# Server_USB.net
KiCad netlist of a schematic drawn in Altium Designer
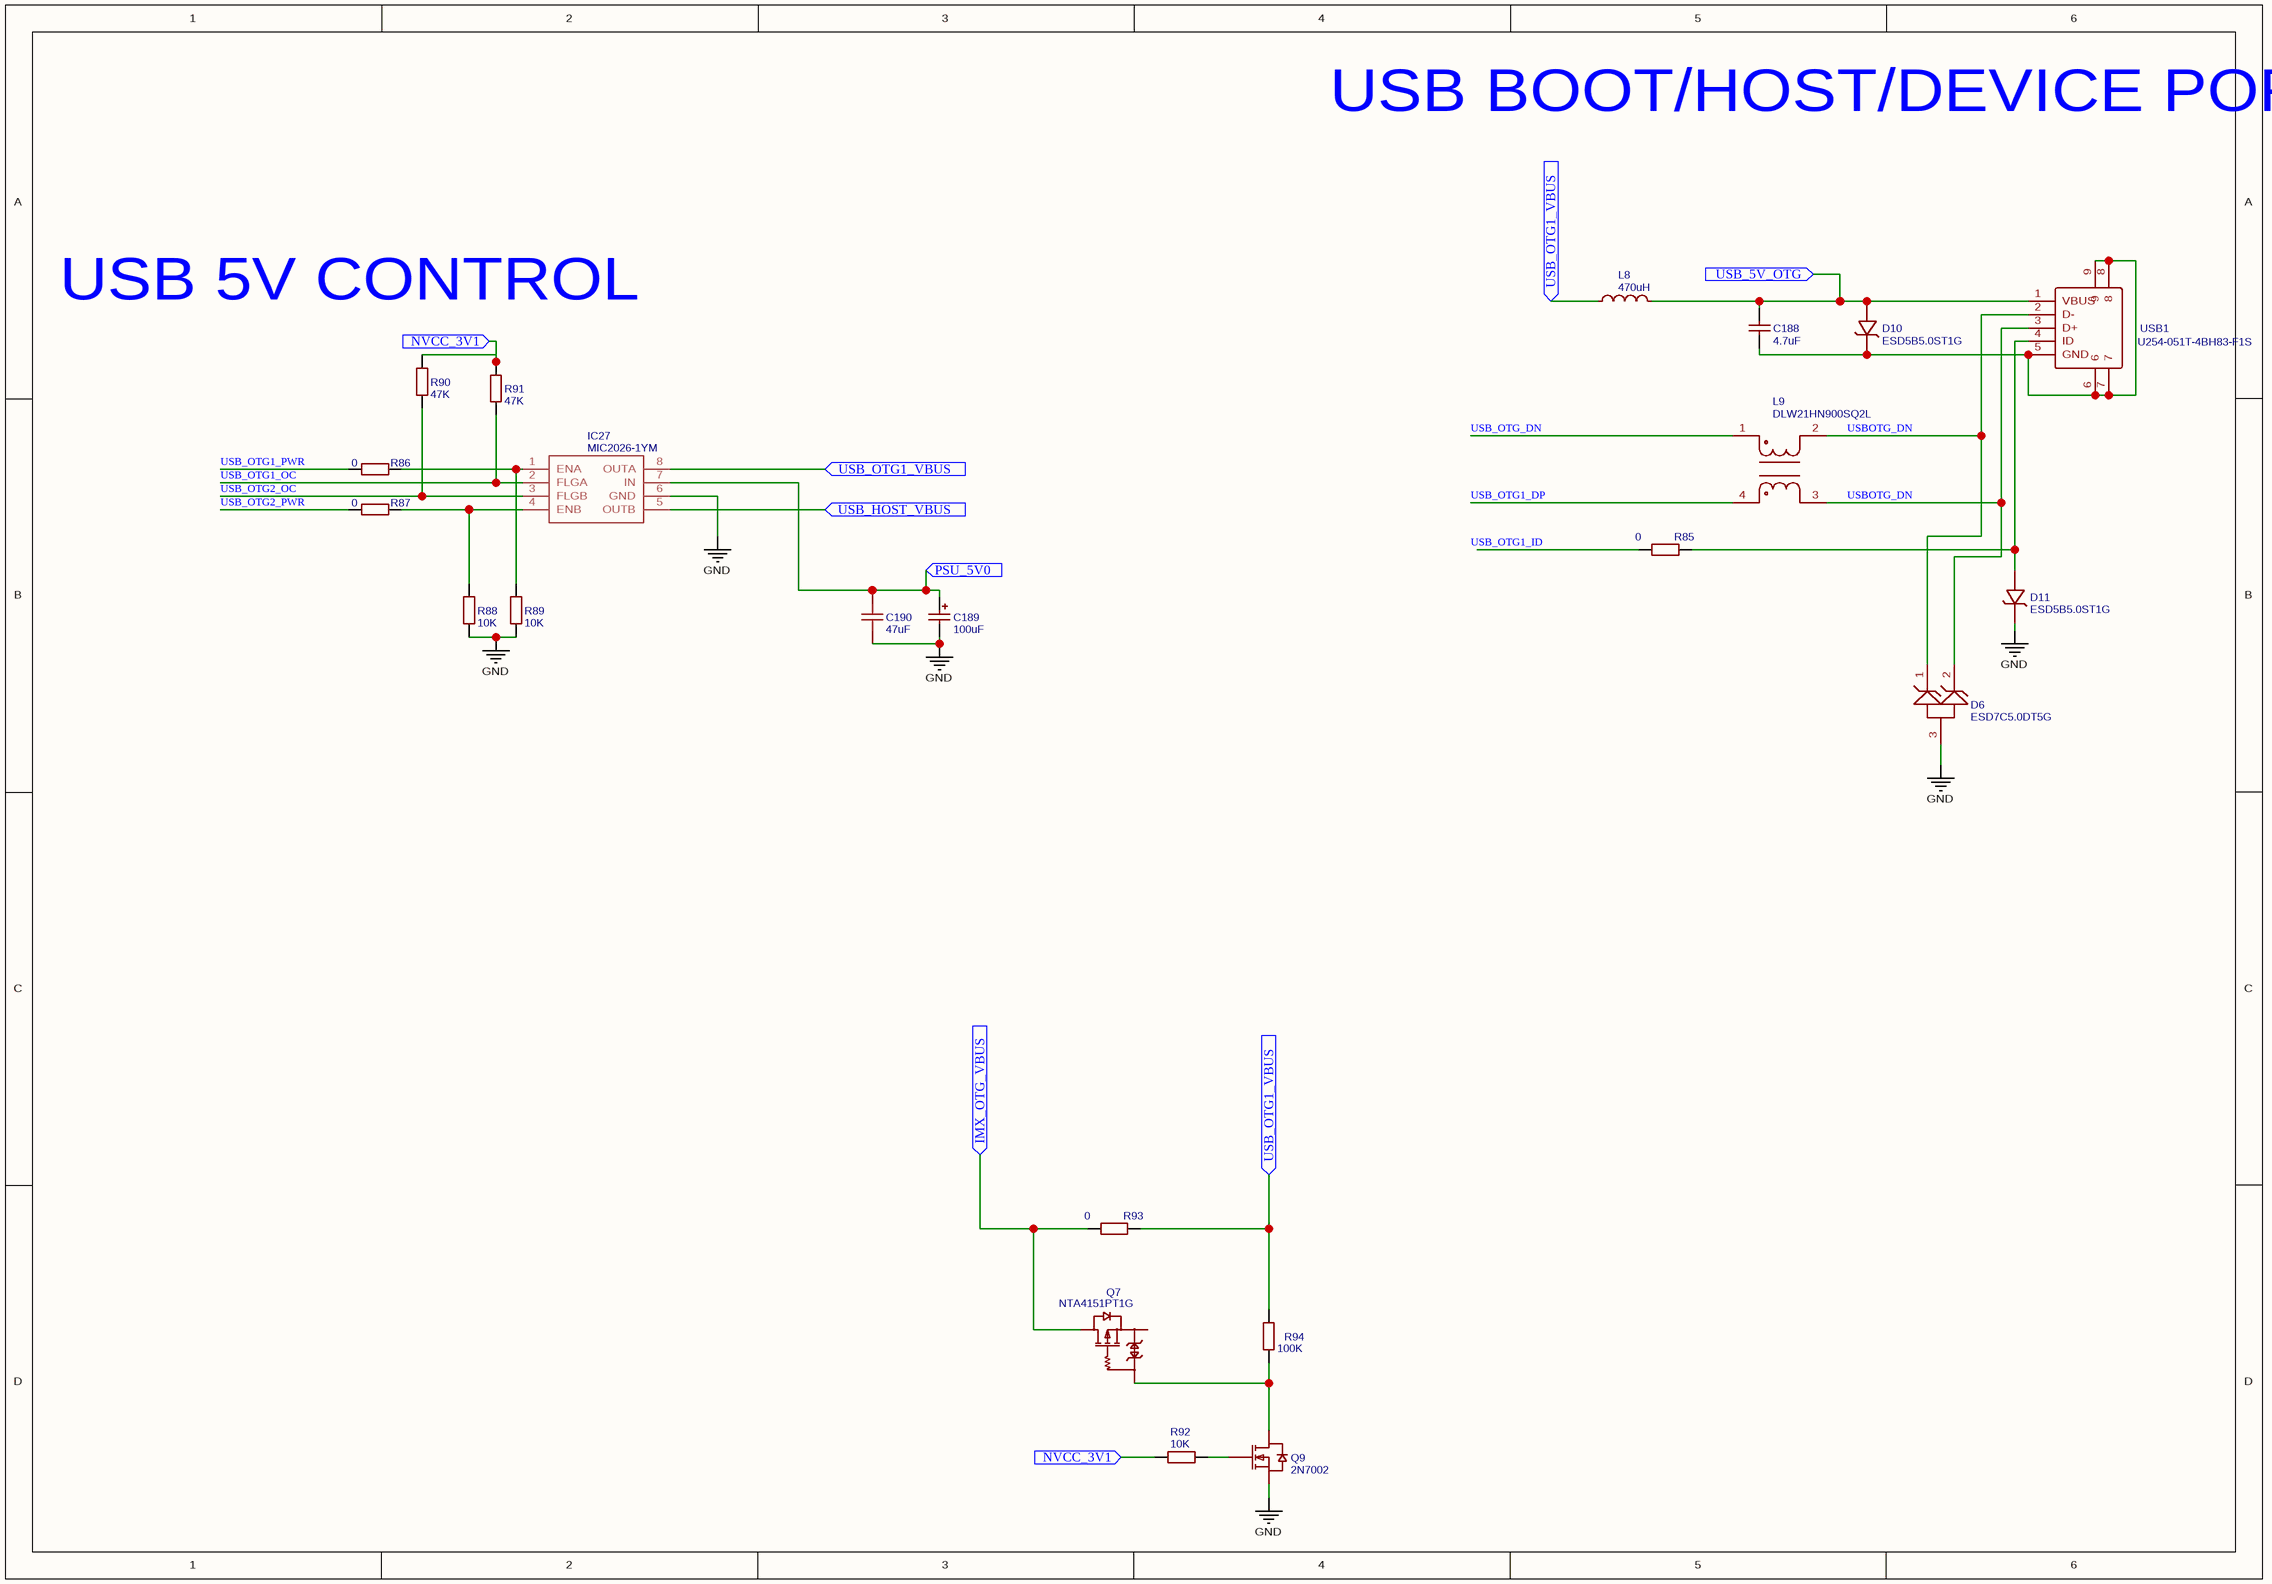
[diagram p0: Server USB.schdoc]

(export (version "E")
  (design (tool "Eeschema 10.0.6"))
  (components
    (comp (ref "C188")
      (value "4.7uF")
      (fields
        (field (name "BOM_MANUFACTURER PART") "CL05A475MP5NRNC")
        (field (name "BOM_SUPPLIER PART") "C23733")
      )
      (libsource (lib "altium-import") (part "root_1_4.7uF_"))
    )
    (comp (ref "C189")
      (value "100uF")
      (fields
        (field (name "BOM_MANUFACTURER PART") "TAJE107M025RNJ")
        (field (name "BOM_SUPPLIER PART") "C7230")
      )
      (libsource (lib "altium-import") (part "root_1_100uF_"))
    )
    (comp (ref "C190")
      (value "47uF")
      (fields
        (field (name "BOM_MANUFACTURER PART") "CL31A476MPHNNNE")
        (field (name "BOM_SUPPLIER PART") "C96123")
      )
      (libsource (lib "altium-import") (part "root_1_47uF_"))
    )
    (comp (ref "D6") (value "ESD7C5.0DT5G") (libsource (lib "altium-import") (part "root_1_ESD7C5.0DT5G_")))
    (comp (ref "D10")
      (value "ESD5B5.0ST1G")
      (fields (field (name "BOM_SUPPLIER PART") "C93623"))
      (libsource (lib "altium-import") (part "root_1_ESD5B5.0ST1G_"))
    )
    (comp (ref "D11")
      (value "ESD5B5.0ST1G")
      (fields (field (name "BOM_SUPPLIER PART") "C93623"))
      (libsource (lib "altium-import") (part "root_1_ESD5B5.0ST1G_"))
    )
    (comp (ref "IC27")
      (value "MIC2026-1YM")
      (fields (field (name "CONTRIBUTOR") "Ke'Ondrae_Mell"))
      (libsource (lib "altium-import") (part "root_0_MIC2026-1YM_"))
    )
    (comp (ref "L8")
      (value "470uH")
      (fields
        (field (name "BOM_SUPPLIER PART") "C169393")
        (field (name "BOM_MANUFACTURER PART") "SWRB1205S-471MT")
        (field (name "CONTRIBUTOR") "LCSC")
      )
      (libsource (lib "altium-import") (part "root_0_470uH_"))
    )
    (comp (ref "L9")
      (value "DLW21HN900SQ2L")
      (fields (field (name "BOM_SUPPLIER PART") "C97235"))
      (libsource (lib "altium-import") (part "root_0_DLW21HN900SQ2L_"))
    )
    (comp (ref "Q7")
      (value "NTA4151PT1G")
      (fields (field (name "BOM_SUPPLIER PART") "C54876"))
      (libsource (lib "altium-import") (part "root_1_NTA4151PT1G_"))
    )
    (comp (ref "Q9")
      (value "2N7002")
      (fields (field (name "BOM_SUPPLIER PART") "C8545"))
      (libsource (lib "altium-import") (part "root_0_2N7002_"))
    )
    (comp (ref "R85")
      (value "0")
      (fields
        (field (name "BOM_MANUFACTURER PART") "RK73Z1ETTP")
        (field (name "BOM_SUPPLIER PART") "C131359")
      )
      (libsource (lib "altium-import") (part "root_0_0_"))
    )
    (comp (ref "R86")
      (value "0")
      (fields
        (field (name "BOM_MANUFACTURER PART") "RK73Z1ETTP")
        (field (name "BOM_SUPPLIER PART") "C131359")
      )
      (libsource (lib "altium-import") (part "root_0_0_"))
    )
    (comp (ref "R87")
      (value "0")
      (fields
        (field (name "BOM_MANUFACTURER PART") "RK73Z1ETTP")
        (field (name "BOM_SUPPLIER PART") "C131359")
      )
      (libsource (lib "altium-import") (part "root_0_0_"))
    )
    (comp (ref "R88")
      (value "10K")
      (fields
        (field (name "BOM_MANUFACTURER PART") "0603WAF1002T5E")
        (field (name "BOM_SUPPLIER PART") "C25804")
      )
      (libsource (lib "altium-import") (part "root_1_10K_"))
    )
    (comp (ref "R89")
      (value "10K")
      (fields
        (field (name "BOM_MANUFACTURER PART") "0603WAF1002T5E")
        (field (name "BOM_SUPPLIER PART") "C25804")
      )
      (libsource (lib "altium-import") (part "root_1_10K_"))
    )
    (comp (ref "R90")
      (value "47K")
      (fields
        (field (name "BOM_MANUFACTURER PART") "0603WAF4702T5E")
        (field (name "BOM_SUPPLIER PART") "C25819")
      )
      (libsource (lib "altium-import") (part "root_1_47K_"))
    )
    (comp (ref "R91")
      (value "47K")
      (fields
        (field (name "BOM_MANUFACTURER PART") "0603WAF4702T5E")
        (field (name "BOM_SUPPLIER PART") "C25819")
      )
      (libsource (lib "altium-import") (part "root_1_47K_"))
    )
    (comp (ref "R92")
      (value "10K")
      (fields
        (field (name "BOM_MANUFACTURER PART") "0603WAF1002T5E")
        (field (name "BOM_SUPPLIER PART") "C25804")
      )
      (libsource (lib "altium-import") (part "root_2_10K_"))
    )
    (comp (ref "R93")
      (value "0")
      (fields
        (field (name "BOM_MANUFACTURER PART") "RK73Z1ETTP")
        (field (name "BOM_SUPPLIER PART") "C131359")
      )
      (libsource (lib "altium-import") (part "root_0_0_"))
    )
    (comp (ref "R94")
      (value "100K")
      (fields
        (field (name "BOM_MANUFACTURER PART") "0603WAF1003T5E")
        (field (name "BOM_SUPPLIER PART") "C25803")
      )
      (libsource (lib "altium-import") (part "root_1_100K_"))
    )
    (comp (ref "USB1")
      (value "U254-051T-4BH83-F1S")
      (fields (field (name "BOM_SUPPLIER PART") "C397452") (field (name "CONTRIBUTOR") "LCSC"))
      (libsource (lib "altium-import") (part "root_0_U254-051T-4BH83-F1S_"))
    )
  )
  (nets
    (net (code "1") (name "/IMX_OTG_VBUS") (class "Default")
      (node (ref "Q7") (pin "3") (pinfunction "D_3") (pintype "passive"))
      (node (ref "R93") (pin "1") (pinfunction "1_1") (pintype "passive"))
    )
    (net (code "2") (name "/NVCC_3V1") (class "Default")
      (node (ref "R90") (pin "2") (pinfunction "2_2") (pintype "passive"))
      (node (ref "R91") (pin "2") (pinfunction "2_2") (pintype "passive"))
      (node (ref "R92") (pin "2") (pinfunction "2_2") (pintype "passive"))
    )
    (net (code "3") (name "/PSU_5V0") (class "Default")
      (node (ref "C189") (pin "1") (pinfunction "1_1") (pintype "passive"))
      (node (ref "C190") (pin "2") (pinfunction "2_2") (pintype "passive"))
      (node (ref "IC27") (pin "7") (pinfunction "IN_7") (pintype "passive"))
    )
    (net (code "4") (name "/USBOTG_DN") (class "Default")
      (node (ref "D6") (pin "1") (pinfunction "K1_1") (pintype "passive"))
      (node (ref "D6") (pin "2") (pinfunction "K2_2") (pintype "passive"))
      (node (ref "L9") (pin "2") (pinfunction "2_2") (pintype "passive"))
      (node (ref "L9") (pin "3") (pinfunction "3_3") (pintype "passive"))
      (node (ref "USB1") (pin "2") (pinfunction "D-_2") (pintype "passive"))
      (node (ref "USB1") (pin "3") (pinfunction "D+_3") (pintype "passive"))
    )
    (net (code "5") (name "/USB_5V_OTG") (class "Default")
      (node (ref "C188") (pin "2") (pinfunction "2_2") (pintype "passive"))
      (node (ref "D10") (pin "2") (pinfunction "A_2") (pintype "passive"))
      (node (ref "L8") (pin "2") (pinfunction "2_2") (pintype "passive"))
      (node (ref "USB1") (pin "1") (pinfunction "VBUS_1") (pintype "passive"))
    )
    (net (code "6") (name "/USB_HOST_VBUS") (class "Default")
      (node (ref "IC27") (pin "5") (pinfunction "OUTB_5") (pintype "passive"))
    )
    (net (code "7") (name "/USB_OTG1_DP") (class "Default")
      (node (ref "L9") (pin "4") (pinfunction "4_4") (pintype "passive"))
    )
    (net (code "9") (name "/USB_OTG1_OC") (class "Default")
      (node (ref "IC27") (pin "2") (pinfunction "FLGA_2") (pintype "passive"))
      (node (ref "R91") (pin "1") (pinfunction "1_1") (pintype "passive"))
    )
    (net (code "10") (name "/USB_OTG1_PWR") (class "Default")
      (node (ref "R86") (pin "1") (pinfunction "1_1") (pintype "passive"))
    )
    (net (code "11") (name "/USB_OTG1_VBUS") (class "Default")
      (node (ref "IC27") (pin "8") (pinfunction "OUTA_8") (pintype "passive"))
      (node (ref "L8") (pin "1") (pinfunction "1_1") (pintype "passive"))
      (node (ref "R93") (pin "2") (pinfunction "2_2") (pintype "passive"))
      (node (ref "R94") (pin "2") (pinfunction "2_2") (pintype "passive"))
    )
    (net (code "12") (name "/USB_OTG2_OC") (class "Default")
      (node (ref "IC27") (pin "3") (pinfunction "FLGB_3") (pintype "passive"))
      (node (ref "R90") (pin "1") (pinfunction "1_1") (pintype "passive"))
    )
    (net (code "13") (name "/USB_OTG2_PWR") (class "Default")
      (node (ref "R87") (pin "1") (pinfunction "1_1") (pintype "passive"))
    )
    (net (code "14") (name "/USB_OTG_DN") (class "Default")
      (node (ref "L9") (pin "1") (pinfunction "1_1") (pintype "passive"))
    )
    (net (code "15") (name "GND") (class "Default")
      (node (ref "C189") (pin "2") (pinfunction "2_2") (pintype "passive"))
      (node (ref "C190") (pin "1") (pinfunction "1_1") (pintype "passive"))
      (node (ref "D11") (pin "1") (pinfunction "C_1") (pintype "passive"))
      (node (ref "D6") (pin "3") (pinfunction "A_3") (pintype "passive"))
      (node (ref "IC27") (pin "6") (pinfunction "GND_6") (pintype "passive"))
      (node (ref "Q9") (pin "2") (pinfunction "S_2") (pintype "passive"))
      (node (ref "R88") (pin "1") (pinfunction "1_1") (pintype "passive"))
      (node (ref "R89") (pin "1") (pinfunction "1_1") (pintype "passive"))
    )
    (net (code "16") (name "Net-(D10-C)") (class "Default")
      (node (ref "C188") (pin "1") (pinfunction "1_1") (pintype "passive"))
      (node (ref "D10") (pin "1") (pinfunction "C_1") (pintype "passive"))
      (node (ref "USB1") (pin "5") (pinfunction "GND_5") (pintype "passive"))
      (node (ref "USB1") (pin "6") (pinfunction "6_6") (pintype "passive"))
      (node (ref "USB1") (pin "7") (pinfunction "7_7") (pintype "passive"))
      (node (ref "USB1") (pin "8") (pinfunction "8_8") (pintype "passive"))
      (node (ref "USB1") (pin "9") (pinfunction "9_9") (pintype "passive"))
    )
    (net (code "17") (name "Net-(D11-A)") (class "Default")
      (node (ref "D11") (pin "2") (pinfunction "A_2") (pintype "passive"))
      (node (ref "R85") (pin "2") (pinfunction "2_2") (pintype "passive"))
      (node (ref "USB1") (pin "4") (pinfunction "ID_4") (pintype "passive"))
    )
    (net (code "18") (name "Net-(IC27-ENA)") (class "Default")
      (node (ref "IC27") (pin "1") (pinfunction "ENA_1") (pintype "passive"))
      (node (ref "R86") (pin "2") (pinfunction "2_2") (pintype "passive"))
      (node (ref "R89") (pin "2") (pinfunction "2_2") (pintype "passive"))
    )
    (net (code "19") (name "Net-(IC27-ENB)") (class "Default")
      (node (ref "IC27") (pin "4") (pinfunction "ENB_4") (pintype "passive"))
      (node (ref "R87") (pin "2") (pinfunction "2_2") (pintype "passive"))
      (node (ref "R88") (pin "2") (pinfunction "2_2") (pintype "passive"))
    )
    (net (code "20") (name "Net-(Q7-G)") (class "Default")
      (node (ref "Q7") (pin "1") (pinfunction "G_1") (pintype "passive"))
      (node (ref "Q9") (pin "3") (pinfunction "D_3") (pintype "passive"))
      (node (ref "R94") (pin "1") (pinfunction "1_1") (pintype "passive"))
    )
    (net (code "21") (name "Net-(Q9-G)") (class "Default")
      (node (ref "Q9") (pin "1") (pinfunction "G_1") (pintype "passive"))
      (node (ref "R92") (pin "1") (pinfunction "1_1") (pintype "passive"))
    )
    (net (code "22") (name "unconnected-(Q7-S-Pad2)") (class "Default")
      (node (ref "Q7") (pin "2") (pinfunction "S_2") (pintype "passive"))
    )
    (net (code "23") (name "unconnected-(R85-Pad1)") (class "Default")
      (node (ref "R85") (pin "1") (pinfunction "1_1") (pintype "passive"))
    )
  )
)
